# 07sdcard.net
KiCad netlist of a schematic drawn in Altium Designer
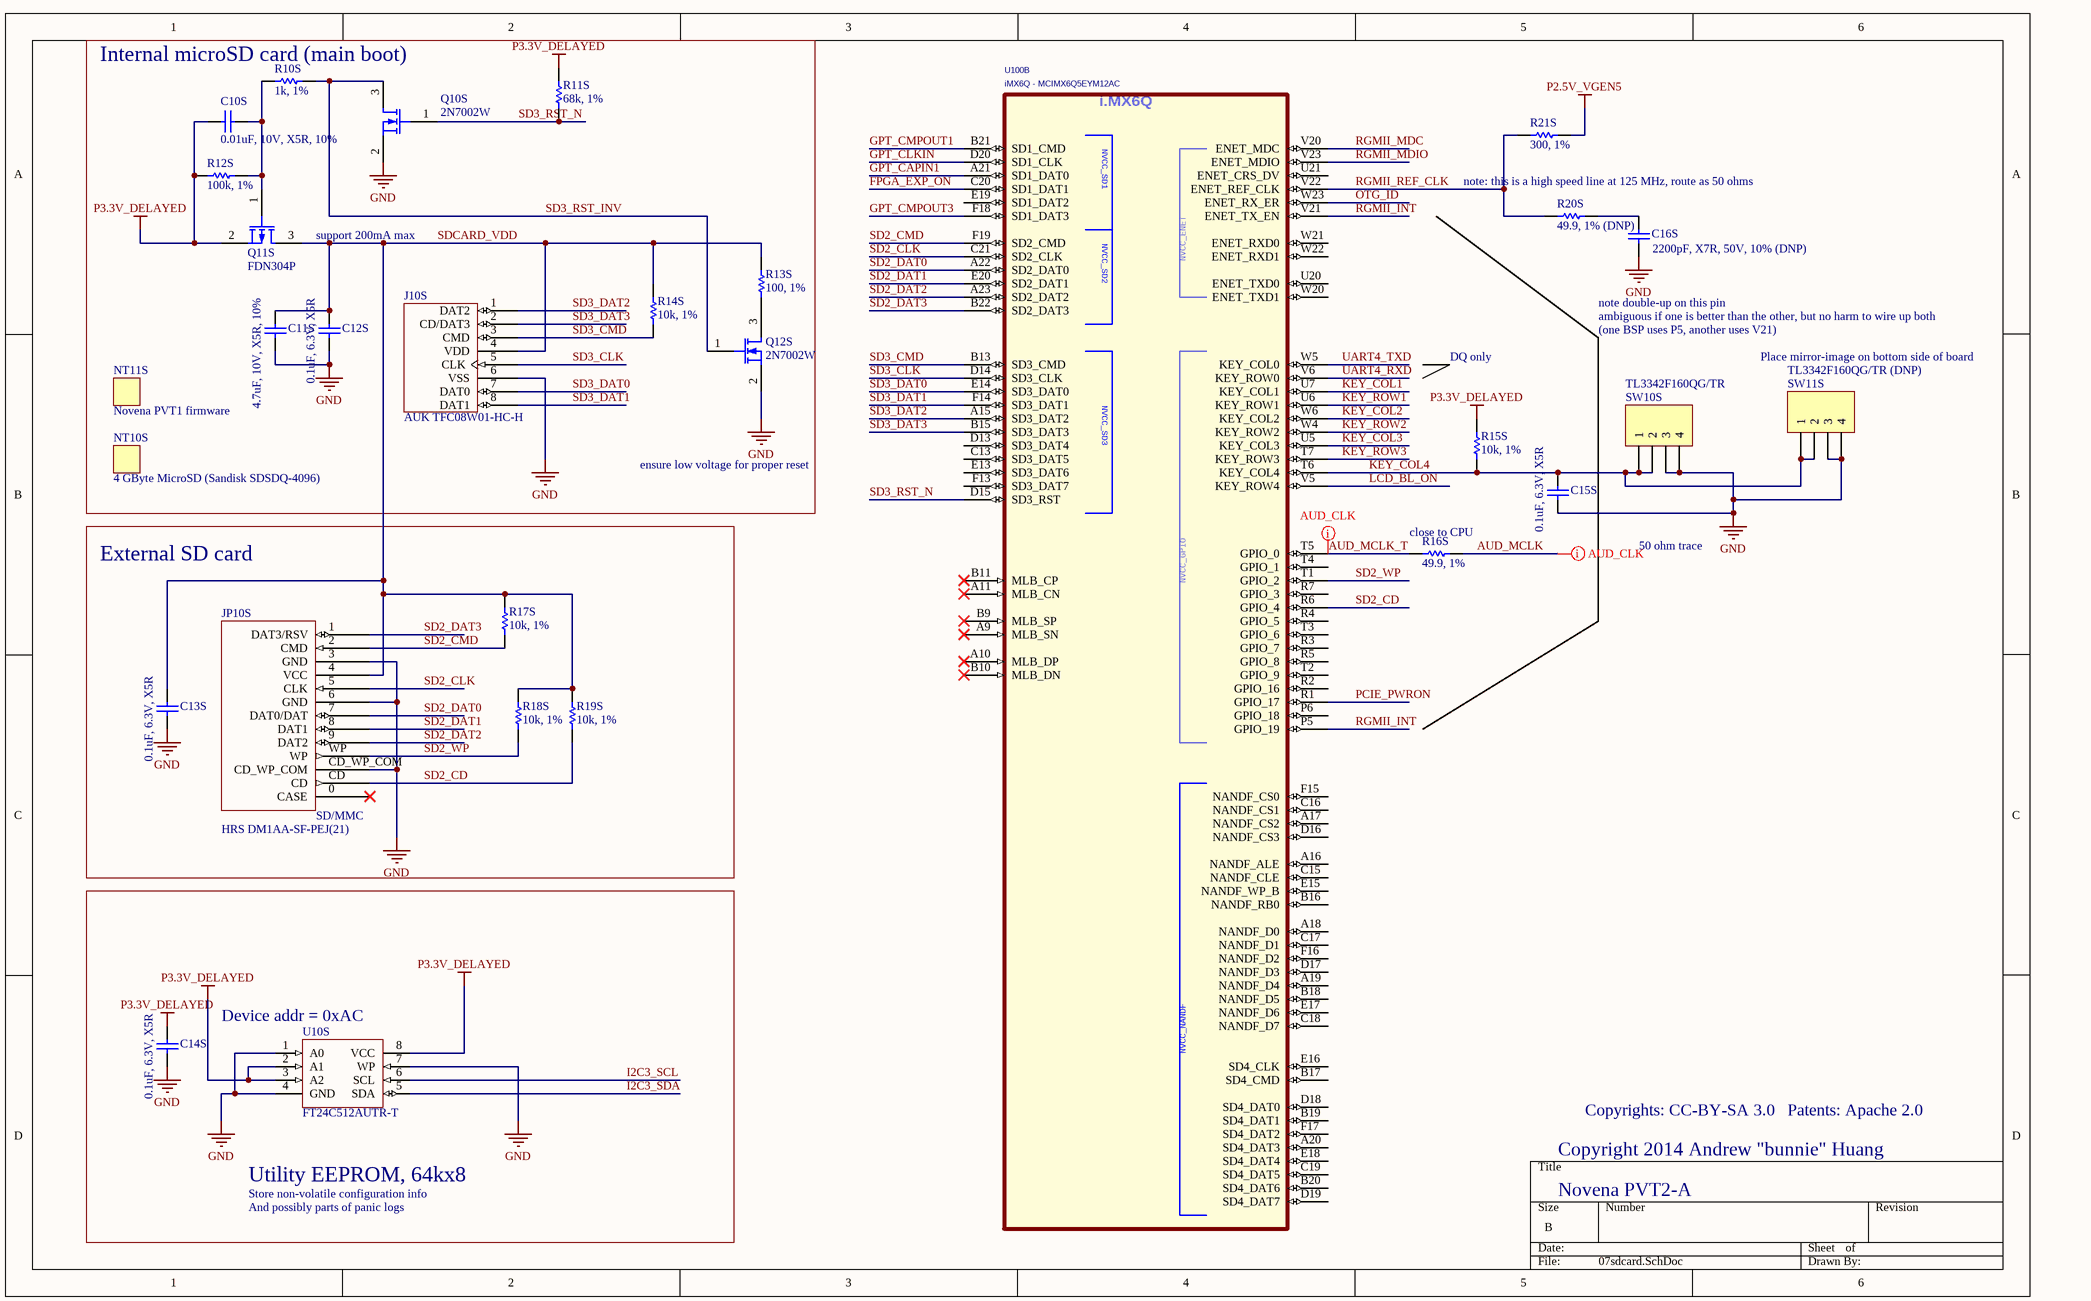
[diagram p0: 07sdcard.SchDoc]

(export (version "E")
  (design (tool "Eeschema 10.0.6"))
  (components
    (comp (ref "C10S")
      (value "0.01uF, 10V, X5R, 10%")
      (footprint "CAPC0603N_B")
      (description "Capacitor (Semiconductor SIM Model)")
      (fields (field (name "PUBLISHER") "Altium Limited"))
      (libsource (lib "Miscellaneous Devices") (part "Cap Semi"))
    )
    (comp (ref "C11S")
      (value "4.7uF, 10V, X5R, 10%")
      (footprint "CAPC1608N")
      (description "Capacitor (Semiconductor SIM Model)")
      (fields (field (name "PUBLISHER") "Altium Limited"))
      (libsource (lib "Miscellaneous Devices") (part "Cap Semi"))
    )
    (comp (ref "C12S")
      (value "0.1uF, 6.3V, X5R")
      (footprint "CAPC0603N_B")
      (description "Capacitor (Semiconductor SIM Model)")
      (fields (field (name "PUBLISHER") "Altium Limited"))
      (libsource (lib "Miscellaneous Devices") (part "Cap Semi"))
    )
    (comp (ref "C13S")
      (value "0.1uF, 6.3V, X5R")
      (footprint "CAPC0603N_B")
      (description "Capacitor (Semiconductor SIM Model)")
      (fields (field (name "PUBLISHER") "Altium Limited"))
      (libsource (lib "Miscellaneous Devices") (part "Cap Semi"))
    )
    (comp (ref "C14S")
      (value "0.1uF, 6.3V, X5R")
      (footprint "CAPC0603N_B")
      (description "Capacitor (Semiconductor SIM Model)")
      (fields (field (name "PUBLISHER") "Altium Limited"))
      (libsource (lib "Miscellaneous Devices") (part "Cap Semi"))
    )
    (comp (ref "C15S")
      (value "0.1uF, 6.3V, X5R")
      (footprint "CAPC0603N_B")
      (description "Capacitor (Semiconductor SIM Model)")
      (fields (field (name "PUBLISHER") "Altium Limited"))
      (libsource (lib "Miscellaneous Devices") (part "Cap Semi"))
    )
    (comp (ref "C16S")
      (value "2200pF, X7R, 50V, 10% (DNP)")
      (footprint "CAPC1005N")
      (description "Capacitor (Semiconductor SIM Model)")
      (fields (field (name "PUBLISHER") "Altium Limited"))
      (libsource (lib "Miscellaneous Devices") (part "Cap Semi"))
    )
    (comp (ref "J10S")
      (value "AUK TFC08W01-HC-H")
      (footprint "AUK_TFC08W01-HC-H")
      (description "Captive Micro-SD card for firmware images")
      (libsource (lib "commonsch") (part "MICRO_SD"))
    )
    (comp (ref "JP10S")
      (value "HRS DM1AA-SF-PEJ(21)")
      (footprint "HRS_DM1AA_SF_PEJ(21)")
      (description "SD card connector")
      (libsource (lib "commonsch") (part "HRS_DM1AA_SF_PEJ(21)"))
    )
    (comp (ref "NT10S")
      (value "4 GByte MicroSD (Sandisk SDSDQ-4096)")
      (description "Placeholder for non-electrical BOM items")
      (libsource (lib "commonsch") (part "NOTE"))
    )
    (comp (ref "NT11S")
      (value "Novena PVT1 firmware")
      (description "Placeholder for non-electrical BOM items")
      (libsource (lib "commonsch") (part "NOTE"))
    )
    (comp (ref "Q10S")
      (value "2N7002W")
      (footprint "SOT323-3AN")
      (description "N-Channel MOSFET")
      (fields (field (name "PUBLISHER") "Altium Limited"))
      (libsource (lib "Miscellaneous Devices") (part "MOSFET-N"))
    )
    (comp (ref "Q11S")
      (value "FDN304P")
      (footprint "SOT23-3N")
      (description "P-Channel MOSFET")
      (fields (field (name "PUBLISHER") "Altium Limited"))
      (libsource (lib "Miscellaneous Devices") (part "MOSFET-P"))
    )
    (comp (ref "Q12S")
      (value "2N7002W")
      (footprint "SOT323-3AN")
      (description "N-Channel MOSFET")
      (fields (field (name "PUBLISHER") "Altium Limited"))
      (libsource (lib "Miscellaneous Devices") (part "MOSFET-N"))
    )
    (comp (ref "R10S")
      (value "1k, 1%")
      (footprint "RESC1005N")
      (description "Resistor")
      (fields (field (name "PUBLISHER") "Altium Limited"))
      (libsource (lib "Miscellaneous Devices") (part "Res1"))
    )
    (comp (ref "R11S")
      (value "68k, 1%")
      (footprint "RESC1005N")
      (description "Resistor")
      (fields (field (name "PUBLISHER") "Altium Limited"))
      (libsource (lib "Miscellaneous Devices") (part "Res1"))
    )
    (comp (ref "R12S")
      (value "100k, 1%")
      (footprint "RESC1005N")
      (description "Resistor")
      (fields (field (name "PUBLISHER") "Altium Limited"))
      (libsource (lib "Miscellaneous Devices") (part "Res1"))
    )
    (comp (ref "R13S")
      (value "100, 1%")
      (footprint "RESC1005N")
      (description "Resistor")
      (fields (field (name "PUBLISHER") "Altium Limited"))
      (libsource (lib "Miscellaneous Devices") (part "Res1"))
    )
    (comp (ref "R14S")
      (value "10k, 1%")
      (footprint "RESC1005N")
      (description "Resistor")
      (fields (field (name "PUBLISHER") "Altium Limited"))
      (libsource (lib "Miscellaneous Devices") (part "Res1"))
    )
    (comp (ref "R15S")
      (value "10k, 1%")
      (footprint "RESC1005N")
      (description "Resistor")
      (fields (field (name "PUBLISHER") "Altium Limited"))
      (libsource (lib "Miscellaneous Devices") (part "Res1"))
    )
    (comp (ref "R16S")
      (value "49.9, 1%")
      (footprint "RESC1005N")
      (description "Resistor")
      (fields (field (name "PUBLISHER") "Altium Limited"))
      (libsource (lib "Miscellaneous Devices") (part "Res1"))
    )
    (comp (ref "R17S")
      (value "10k, 1%")
      (footprint "RESC1005N")
      (description "Resistor")
      (fields (field (name "PUBLISHER") "Altium Limited"))
      (libsource (lib "Miscellaneous Devices") (part "Res1"))
    )
    (comp (ref "R18S")
      (value "10k, 1%")
      (footprint "RESC1005N")
      (description "Resistor")
      (fields (field (name "PUBLISHER") "Altium Limited"))
      (libsource (lib "Miscellaneous Devices") (part "Res1"))
    )
    (comp (ref "R19S")
      (value "10k, 1%")
      (footprint "RESC1005N")
      (description "Resistor")
      (fields (field (name "PUBLISHER") "Altium Limited"))
      (libsource (lib "Miscellaneous Devices") (part "Res1"))
    )
    (comp (ref "R20S")
      (value "49.9, 1% (DNP)")
      (footprint "RESC1005N")
      (description "Resistor")
      (fields (field (name "PUBLISHER") "Altium Limited"))
      (libsource (lib "Miscellaneous Devices") (part "Res1"))
    )
    (comp (ref "R21S")
      (value "300, 1%")
      (footprint "RESC1005N")
      (description "Resistor")
      (fields (field (name "PUBLISHER") "Altium Limited"))
      (libsource (lib "Miscellaneous Devices") (part "Res1"))
    )
    (comp (ref "SW10S")
      (value "TL3342F160QG/TR")
      (footprint "SWITCH_TS-1187A")
      (description "Chi Fung TS-1187A")
      (fields (field (name "PUBLISHER") "Altium Limited"))
      (libsource (lib "Miscellaneous Connectors") (part "Header 4"))
    )
    (comp (ref "SW11S")
      (value "TL3342F160QG/TR (DNP)")
      (footprint "SWITCH_TS-1187A")
      (description "Chi Fung TS-1187A")
      (fields (field (name "PUBLISHER") "Altium Limited"))
      (libsource (lib "Miscellaneous Connectors") (part "Header 4"))
    )
    (comp (ref "U10S")
      (value "FT24C512AUTR-T")
      (footprint "TSOP65P640-8AN")
      (description "8kbit (1kx8) I2C EEPROM")
      (libsource (lib "*") (part "AT24C08"))
    )
    (comp (ref "U100")
      (value "iMX6Q - MCIMX6Q5EYM12AC")
      (description "PCIMX6Q5EVT10AC")
      (libsource (lib "*") (part "PCIMX6Q6VV1A"))
    )
  )
  (nets
    (net (code "1") (name "/AUD_MCLK") (class "Default")
      (node (ref "R16S") (pin "1") (pinfunction "1_1") (pintype "passive"))
    )
    (net (code "2") (name "/AUD_MCLK_T") (class "Default")
      (node (ref "R16S") (pin "2") (pinfunction "2_2") (pintype "passive"))
      (node (ref "U100") (pin "T5") (pinfunction "GPIO_0_T5") (pintype "bidirectional"))
    )
    (net (code "3") (name "/FPGA_EXP_ON") (class "Default")
      (node (ref "U100") (pin "C20") (pinfunction "SD1_DAT1_C20") (pintype "bidirectional"))
    )
    (net (code "4") (name "/GPT_CAPIN1") (class "Default")
      (node (ref "U100") (pin "A21") (pinfunction "SD1_DAT0_A21") (pintype "bidirectional"))
    )
    (net (code "5") (name "/GPT_CLKIN") (class "Default")
      (node (ref "U100") (pin "D20") (pinfunction "SD1_CLK_D20") (pintype "bidirectional"))
    )
    (net (code "6") (name "/GPT_CMPOUT1") (class "Default")
      (node (ref "U100") (pin "B21") (pinfunction "SD1_CMD_B21") (pintype "bidirectional"))
    )
    (net (code "7") (name "/GPT_CMPOUT3") (class "Default")
      (node (ref "U100") (pin "F18") (pinfunction "SD1_DAT3_F18") (pintype "bidirectional"))
    )
    (net (code "8") (name "/I2C3_SCL") (class "Default")
      (node (ref "U10S") (pin "6") (pinfunction "SCL_6") (pintype "input"))
    )
    (net (code "9") (name "/I2C3_SDA") (class "Default")
      (node (ref "U10S") (pin "5") (pinfunction "SDA_5") (pintype "bidirectional"))
    )
    (net (code "10") (name "/KEY_COL1") (class "Default")
      (node (ref "U100") (pin "U7") (pinfunction "KEY_COL1_U7") (pintype "bidirectional"))
    )
    (net (code "11") (name "/KEY_COL2") (class "Default")
      (node (ref "U100") (pin "W6") (pinfunction "KEY_COL2_W6") (pintype "bidirectional"))
    )
    (net (code "12") (name "/KEY_COL3") (class "Default")
      (node (ref "U100") (pin "U5") (pinfunction "KEY_COL3_U5") (pintype "bidirectional"))
    )
    (net (code "13") (name "/KEY_COL4") (class "Default")
      (node (ref "C15S") (pin "1") (pinfunction "1_1") (pintype "passive"))
      (node (ref "R15S") (pin "2") (pinfunction "2_2") (pintype "passive"))
      (node (ref "SW10S") (pin "1") (pinfunction "1_1") (pintype "passive"))
      (node (ref "SW10S") (pin "2") (pinfunction "2_2") (pintype "passive"))
      (node (ref "SW11S") (pin "1") (pinfunction "1_1") (pintype "passive"))
      (node (ref "SW11S") (pin "2") (pinfunction "2_2") (pintype "passive"))
      (node (ref "U100") (pin "T6") (pinfunction "KEY_COL4_T6") (pintype "bidirectional"))
    )
    (net (code "14") (name "/KEY_ROW1") (class "Default")
      (node (ref "U100") (pin "U6") (pinfunction "KEY_ROW1_U6") (pintype "bidirectional"))
    )
    (net (code "15") (name "/KEY_ROW2") (class "Default")
      (node (ref "U100") (pin "W4") (pinfunction "KEY_ROW2_W4") (pintype "bidirectional"))
    )
    (net (code "16") (name "/KEY_ROW3") (class "Default")
      (node (ref "U100") (pin "T7") (pinfunction "KEY_ROW3_T7") (pintype "bidirectional"))
    )
    (net (code "17") (name "/LCD_BL_ON") (class "Default")
      (node (ref "U100") (pin "V5") (pinfunction "KEY_ROW4_V5") (pintype "bidirectional"))
    )
    (net (code "18") (name "/OTG_ID") (class "Default")
      (node (ref "U100") (pin "W23") (pinfunction "ENET_RX_ER_W23") (pintype "bidirectional"))
    )
    (net (code "19") (name "/PCIE_PWRON") (class "Default")
      (node (ref "U100") (pin "R1") (pinfunction "GPIO_17_R1") (pintype "bidirectional"))
    )
    (net (code "20") (name "/RGMII_INT") (class "Default")
      (node (ref "U100") (pin "P5") (pinfunction "GPIO_19_P5") (pintype "bidirectional"))
      (node (ref "U100") (pin "V21") (pinfunction "ENET_TX_EN_V21") (pintype "bidirectional"))
    )
    (net (code "21") (name "/RGMII_MDC") (class "Default")
      (node (ref "U100") (pin "V20") (pinfunction "ENET_MDC_V20") (pintype "bidirectional"))
    )
    (net (code "22") (name "/RGMII_MDIO") (class "Default")
      (node (ref "U100") (pin "V23") (pinfunction "ENET_MDIO_V23") (pintype "bidirectional"))
    )
    (net (code "23") (name "/RGMII_REF_CLK") (class "Default")
      (node (ref "R20S") (pin "1") (pinfunction "1_1") (pintype "passive"))
      (node (ref "R21S") (pin "1") (pinfunction "1_1") (pintype "passive"))
      (node (ref "U100") (pin "V22") (pinfunction "ENET_REF_CLK_V22") (pintype "bidirectional"))
    )
    (net (code "24") (name "/SD2_CD") (class "Default")
      (node (ref "JP10S") (pin "CD") (pinfunction "CD_CD") (pintype "output"))
      (node (ref "R19S") (pin "2") (pinfunction "2_2") (pintype "passive"))
      (node (ref "U100") (pin "R6") (pinfunction "GPIO_4_R6") (pintype "bidirectional"))
    )
    (net (code "25") (name "/SD2_CLK") (class "Default")
      (node (ref "JP10S") (pin "5") (pinfunction "CLK_5") (pintype "input"))
      (node (ref "U100") (pin "C21") (pinfunction "SD2_CLK_C21") (pintype "bidirectional"))
    )
    (net (code "26") (name "/SD2_CMD") (class "Default")
      (node (ref "JP10S") (pin "2") (pinfunction "CMD_2") (pintype "input"))
      (node (ref "R17S") (pin "2") (pinfunction "2_2") (pintype "passive"))
      (node (ref "U100") (pin "F19") (pinfunction "SD2_CMD_F19") (pintype "bidirectional"))
    )
    (net (code "27") (name "/SD2_DAT0") (class "Default")
      (node (ref "JP10S") (pin "7") (pinfunction "DAT0/DAT_7") (pintype "bidirectional"))
      (node (ref "U100") (pin "A22") (pinfunction "SD2_DAT0_A22") (pintype "bidirectional"))
    )
    (net (code "28") (name "/SD2_DAT1") (class "Default")
      (node (ref "JP10S") (pin "8") (pinfunction "DAT1_8") (pintype "bidirectional"))
      (node (ref "U100") (pin "E20") (pinfunction "SD2_DAT1_E20") (pintype "bidirectional"))
    )
    (net (code "29") (name "/SD2_DAT2") (class "Default")
      (node (ref "JP10S") (pin "9") (pinfunction "DAT2_9") (pintype "bidirectional"))
      (node (ref "U100") (pin "A23") (pinfunction "SD2_DAT2_A23") (pintype "bidirectional"))
    )
    (net (code "30") (name "/SD2_DAT3") (class "Default")
      (node (ref "JP10S") (pin "1") (pinfunction "DAT3/RSV_1") (pintype "bidirectional"))
      (node (ref "U100") (pin "B22") (pinfunction "SD2_DAT3_B22") (pintype "bidirectional"))
    )
    (net (code "31") (name "/SD2_WP") (class "Default")
      (node (ref "JP10S") (pin "WP") (pinfunction "WP_WP") (pintype "output"))
      (node (ref "R18S") (pin "2") (pinfunction "2_2") (pintype "passive"))
      (node (ref "U100") (pin "T1") (pinfunction "GPIO_2_T1") (pintype "bidirectional"))
    )
    (net (code "32") (name "/SD3_CLK") (class "Default")
      (node (ref "J10S") (pin "5") (pinfunction "CLK_5") (pintype "input"))
      (node (ref "U100") (pin "D14") (pinfunction "SD3_CLK_D14") (pintype "bidirectional"))
    )
    (net (code "33") (name "/SD3_CMD") (class "Default")
      (node (ref "J10S") (pin "3") (pinfunction "CMD_3") (pintype "bidirectional"))
      (node (ref "R14S") (pin "2") (pinfunction "2_2") (pintype "passive"))
      (node (ref "U100") (pin "B13") (pinfunction "SD3_CMD_B13") (pintype "bidirectional"))
    )
    (net (code "34") (name "/SD3_DAT0") (class "Default")
      (node (ref "J10S") (pin "7") (pinfunction "DAT0_7") (pintype "bidirectional"))
      (node (ref "U100") (pin "E14") (pinfunction "SD3_DAT0_E14") (pintype "bidirectional"))
    )
    (net (code "35") (name "/SD3_DAT1") (class "Default")
      (node (ref "J10S") (pin "8") (pinfunction "DAT1_8") (pintype "bidirectional"))
      (node (ref "U100") (pin "F14") (pinfunction "SD3_DAT1_F14") (pintype "bidirectional"))
    )
    (net (code "36") (name "/SD3_DAT2") (class "Default")
      (node (ref "J10S") (pin "1") (pinfunction "DAT2_1") (pintype "bidirectional"))
      (node (ref "U100") (pin "A15") (pinfunction "SD3_DAT2_A15") (pintype "bidirectional"))
    )
    (net (code "37") (name "/SD3_DAT3") (class "Default")
      (node (ref "J10S") (pin "2") (pinfunction "CD/DAT3_2") (pintype "bidirectional"))
      (node (ref "U100") (pin "B15") (pinfunction "SD3_DAT3_B15") (pintype "bidirectional"))
    )
    (net (code "38") (name "/SD3_RST_INV") (class "Default")
      (node (ref "Q10S") (pin "3") (pinfunction "D_3") (pintype "passive"))
      (node (ref "Q12S") (pin "1") (pinfunction "G_1") (pintype "passive"))
      (node (ref "R10S") (pin "1") (pinfunction "1_1") (pintype "passive"))
    )
    (net (code "39") (name "/SD3_RST_N") (class "Default")
      (node (ref "Q10S") (pin "1") (pinfunction "G_1") (pintype "passive"))
      (node (ref "R11S") (pin "2") (pinfunction "2_2") (pintype "passive"))
      (node (ref "U100") (pin "D15") (pinfunction "SD3_RST_D15") (pintype "bidirectional"))
    )
    (net (code "40") (name "/SDCARD_VDD") (class "Default")
      (node (ref "C11S") (pin "1") (pinfunction "1_1") (pintype "passive"))
      (node (ref "C12S") (pin "1") (pinfunction "1_1") (pintype "passive"))
      (node (ref "C13S") (pin "1") (pinfunction "1_1") (pintype "passive"))
      (node (ref "J10S") (pin "4") (pinfunction "VDD_4") (pintype "power_in"))
      (node (ref "JP10S") (pin "4") (pinfunction "VCC_4") (pintype "power_in"))
      (node (ref "Q11S") (pin "3") (pinfunction "D_3") (pintype "passive"))
      (node (ref "R13S") (pin "1") (pinfunction "1_1") (pintype "passive"))
      (node (ref "R14S") (pin "1") (pinfunction "1_1") (pintype "passive"))
      (node (ref "R17S") (pin "1") (pinfunction "1_1") (pintype "passive"))
      (node (ref "R18S") (pin "1") (pinfunction "1_1") (pintype "passive"))
      (node (ref "R19S") (pin "1") (pinfunction "1_1") (pintype "passive"))
    )
    (net (code "41") (name "/UART4_RXD") (class "Default")
      (node (ref "U100") (pin "V6") (pinfunction "KEY_ROW0_V6") (pintype "bidirectional"))
    )
    (net (code "42") (name "/UART4_TXD") (class "Default")
      (node (ref "U100") (pin "W5") (pinfunction "KEY_COL0_W5") (pintype "bidirectional"))
    )
    (net (code "43") (name "GND") (class "Default")
      (node (ref "C11S") (pin "2") (pinfunction "2_2") (pintype "passive"))
      (node (ref "C12S") (pin "2") (pinfunction "2_2") (pintype "passive"))
      (node (ref "C13S") (pin "2") (pinfunction "2_2") (pintype "passive"))
      (node (ref "C14S") (pin "2") (pinfunction "2_2") (pintype "passive"))
      (node (ref "C15S") (pin "2") (pinfunction "2_2") (pintype "passive"))
      (node (ref "C16S") (pin "1") (pinfunction "1_1") (pintype "passive"))
      (node (ref "J10S") (pin "6") (pinfunction "VSS_6") (pintype "power_in"))
      (node (ref "JP10S") (pin "3") (pinfunction "GND_3") (pintype "power_in"))
      (node (ref "JP10S") (pin "6") (pinfunction "GND_6") (pintype "power_in"))
      (node (ref "JP10S") (pin "CD_WP_COM") (pinfunction "CD_WP_COM_CD_WP_COM") (pintype "power_in"))
      (node (ref "Q10S") (pin "2") (pinfunction "S_2") (pintype "passive"))
      (node (ref "Q12S") (pin "2") (pinfunction "S_2") (pintype "passive"))
      (node (ref "SW10S") (pin "3") (pinfunction "3_3") (pintype "passive"))
      (node (ref "SW10S") (pin "4") (pinfunction "4_4") (pintype "passive"))
      (node (ref "SW11S") (pin "3") (pinfunction "3_3") (pintype "passive"))
      (node (ref "SW11S") (pin "4") (pinfunction "4_4") (pintype "passive"))
      (node (ref "U10S") (pin "1") (pinfunction "A0_1") (pintype "input"))
      (node (ref "U10S") (pin "4") (pinfunction "GND_4") (pintype "power_in"))
      (node (ref "U10S") (pin "7") (pinfunction "WP_7") (pintype "input"))
    )
    (net (code "44") (name "Net-(C16S-Pad2)") (class "Default")
      (node (ref "C16S") (pin "2") (pinfunction "2_2") (pintype "passive"))
      (node (ref "R20S") (pin "2") (pinfunction "2_2") (pintype "passive"))
    )
    (net (code "45") (name "Net-(Q11S-G)") (class "Default")
      (node (ref "C10S") (pin "1") (pinfunction "1_1") (pintype "passive"))
      (node (ref "Q11S") (pin "1") (pinfunction "G_1") (pintype "passive"))
      (node (ref "R10S") (pin "2") (pinfunction "2_2") (pintype "passive"))
      (node (ref "R12S") (pin "1") (pinfunction "1_1") (pintype "passive"))
    )
    (net (code "46") (name "Net-(Q12S-D)") (class "Default")
      (node (ref "Q12S") (pin "3") (pinfunction "D_3") (pintype "passive"))
      (node (ref "R13S") (pin "2") (pinfunction "2_2") (pintype "passive"))
    )
    (net (code "47") (name "P2.5V_VGEN5") (class "Default")
      (node (ref "R21S") (pin "2") (pinfunction "2_2") (pintype "passive"))
    )
    (net (code "48") (name "P3.3V_DELAYED") (class "Default")
      (node (ref "C10S") (pin "2") (pinfunction "2_2") (pintype "passive"))
      (node (ref "C14S") (pin "1") (pinfunction "1_1") (pintype "passive"))
      (node (ref "Q11S") (pin "2") (pinfunction "S_2") (pintype "passive"))
      (node (ref "R11S") (pin "1") (pinfunction "1_1") (pintype "passive"))
      (node (ref "R12S") (pin "2") (pinfunction "2_2") (pintype "passive"))
      (node (ref "R15S") (pin "1") (pinfunction "1_1") (pintype "passive"))
      (node (ref "U10S") (pin "2") (pinfunction "A1_2") (pintype "input"))
      (node (ref "U10S") (pin "3") (pinfunction "A2_3") (pintype "input"))
      (node (ref "U10S") (pin "8") (pinfunction "VCC_8") (pintype "power_in"))
    )
    (net (code "49") (name "unconnected-(JP10S-CASE-Pad0)") (class "Default")
      (node (ref "JP10S") (pin "0") (pinfunction "CASE_0") (pintype "power_in+no_connect"))
    )
    (net (code "50") (name "unconnected-(U100B-ENET_CRS_DV-PadU21)") (class "Default")
      (node (ref "U100") (pin "U21") (pinfunction "ENET_CRS_DV_U21") (pintype "bidirectional"))
    )
    (net (code "51") (name "unconnected-(U100B-ENET_RXD0-PadW21)") (class "Default")
      (node (ref "U100") (pin "W21") (pinfunction "ENET_RXD0_W21") (pintype "bidirectional"))
    )
    (net (code "52") (name "unconnected-(U100B-ENET_RXD1-PadW22)") (class "Default")
      (node (ref "U100") (pin "W22") (pinfunction "ENET_RXD1_W22") (pintype "bidirectional"))
    )
    (net (code "53") (name "unconnected-(U100B-ENET_TXD0-PadU20)") (class "Default")
      (node (ref "U100") (pin "U20") (pinfunction "ENET_TXD0_U20") (pintype "bidirectional"))
    )
    (net (code "54") (name "unconnected-(U100B-ENET_TXD1-PadW20)") (class "Default")
      (node (ref "U100") (pin "W20") (pinfunction "ENET_TXD1_W20") (pintype "bidirectional"))
    )
    (net (code "55") (name "unconnected-(U100B-GPIO_1-PadT4)") (class "Default")
      (node (ref "U100") (pin "T4") (pinfunction "GPIO_1_T4") (pintype "bidirectional"))
    )
    (net (code "56") (name "unconnected-(U100B-GPIO_3-PadR7)") (class "Default")
      (node (ref "U100") (pin "R7") (pinfunction "GPIO_3_R7") (pintype "bidirectional"))
    )
    (net (code "57") (name "unconnected-(U100B-GPIO_5-PadR4)") (class "Default")
      (node (ref "U100") (pin "R4") (pinfunction "GPIO_5_R4") (pintype "bidirectional"))
    )
    (net (code "58") (name "unconnected-(U100B-GPIO_6-PadT3)") (class "Default")
      (node (ref "U100") (pin "T3") (pinfunction "GPIO_6_T3") (pintype "bidirectional"))
    )
    (net (code "59") (name "unconnected-(U100B-GPIO_7-PadR3)") (class "Default")
      (node (ref "U100") (pin "R3") (pinfunction "GPIO_7_R3") (pintype "bidirectional"))
    )
    (net (code "60") (name "unconnected-(U100B-GPIO_8-PadR5)") (class "Default")
      (node (ref "U100") (pin "R5") (pinfunction "GPIO_8_R5") (pintype "bidirectional"))
    )
    (net (code "61") (name "unconnected-(U100B-GPIO_9-PadT2)") (class "Default")
      (node (ref "U100") (pin "T2") (pinfunction "GPIO_9_T2") (pintype "bidirectional"))
    )
    (net (code "62") (name "unconnected-(U100B-GPIO_16-PadR2)") (class "Default")
      (node (ref "U100") (pin "R2") (pinfunction "GPIO_16_R2") (pintype "bidirectional"))
    )
    (net (code "63") (name "unconnected-(U100B-GPIO_18-PadP6)") (class "Default")
      (node (ref "U100") (pin "P6") (pinfunction "GPIO_18_P6") (pintype "bidirectional"))
    )
    (net (code "64") (name "unconnected-(U100B-MLB_CN-PadA11)") (class "Default")
      (node (ref "U100") (pin "A11") (pinfunction "MLB_CN_A11") (pintype "input+no_connect"))
    )
    (net (code "65") (name "unconnected-(U100B-MLB_CP-PadB11)") (class "Default")
      (node (ref "U100") (pin "B11") (pinfunction "MLB_CP_B11") (pintype "input+no_connect"))
    )
    (net (code "66") (name "unconnected-(U100B-MLB_DN-PadB10)") (class "Default")
      (node (ref "U100") (pin "B10") (pinfunction "MLB_DN_B10") (pintype "input+no_connect"))
    )
    (net (code "67") (name "unconnected-(U100B-MLB_DP-PadA10)") (class "Default")
      (node (ref "U100") (pin "A10") (pinfunction "MLB_DP_A10") (pintype "input+no_connect"))
    )
    (net (code "68") (name "unconnected-(U100B-MLB_SN-PadA9)") (class "Default")
      (node (ref "U100") (pin "A9") (pinfunction "MLB_SN_A9") (pintype "input+no_connect"))
    )
    (net (code "69") (name "unconnected-(U100B-MLB_SP-PadB9)") (class "Default")
      (node (ref "U100") (pin "B9") (pinfunction "MLB_SP_B9") (pintype "input+no_connect"))
    )
    (net (code "70") (name "unconnected-(U100B-NANDF_ALE-PadA16)") (class "Default")
      (node (ref "U100") (pin "A16") (pinfunction "NANDF_ALE_A16") (pintype "bidirectional"))
    )
    (net (code "71") (name "unconnected-(U100B-NANDF_CLE-PadC15)") (class "Default")
      (node (ref "U100") (pin "C15") (pinfunction "NANDF_CLE_C15") (pintype "bidirectional"))
    )
    (net (code "72") (name "unconnected-(U100B-NANDF_CS0-PadF15)") (class "Default")
      (node (ref "U100") (pin "F15") (pinfunction "NANDF_CS0_F15") (pintype "bidirectional"))
    )
    (net (code "73") (name "unconnected-(U100B-NANDF_CS1-PadC16)") (class "Default")
      (node (ref "U100") (pin "C16") (pinfunction "NANDF_CS1_C16") (pintype "bidirectional"))
    )
    (net (code "74") (name "unconnected-(U100B-NANDF_CS2-PadA17)") (class "Default")
      (node (ref "U100") (pin "A17") (pinfunction "NANDF_CS2_A17") (pintype "bidirectional"))
    )
    (net (code "75") (name "unconnected-(U100B-NANDF_CS3-PadD16)") (class "Default")
      (node (ref "U100") (pin "D16") (pinfunction "NANDF_CS3_D16") (pintype "bidirectional"))
    )
    (net (code "76") (name "unconnected-(U100B-NANDF_D0-PadA18)") (class "Default")
      (node (ref "U100") (pin "A18") (pinfunction "NANDF_D0_A18") (pintype "bidirectional"))
    )
    (net (code "77") (name "unconnected-(U100B-NANDF_D1-PadC17)") (class "Default")
      (node (ref "U100") (pin "C17") (pinfunction "NANDF_D1_C17") (pintype "bidirectional"))
    )
    (net (code "78") (name "unconnected-(U100B-NANDF_D2-PadF16)") (class "Default")
      (node (ref "U100") (pin "F16") (pinfunction "NANDF_D2_F16") (pintype "bidirectional"))
    )
    (net (code "79") (name "unconnected-(U100B-NANDF_D3-PadD17)") (class "Default")
      (node (ref "U100") (pin "D17") (pinfunction "NANDF_D3_D17") (pintype "bidirectional"))
    )
    (net (code "80") (name "unconnected-(U100B-NANDF_D4-PadA19)") (class "Default")
      (node (ref "U100") (pin "A19") (pinfunction "NANDF_D4_A19") (pintype "bidirectional"))
    )
    (net (code "81") (name "unconnected-(U100B-NANDF_D5-PadB18)") (class "Default")
      (node (ref "U100") (pin "B18") (pinfunction "NANDF_D5_B18") (pintype "bidirectional"))
    )
    (net (code "82") (name "unconnected-(U100B-NANDF_D6-PadE17)") (class "Default")
      (node (ref "U100") (pin "E17") (pinfunction "NANDF_D6_E17") (pintype "bidirectional"))
    )
    (net (code "83") (name "unconnected-(U100B-NANDF_D7-PadC18)") (class "Default")
      (node (ref "U100") (pin "C18") (pinfunction "NANDF_D7_C18") (pintype "bidirectional"))
    )
    (net (code "84") (name "unconnected-(U100B-NANDF_RB0-PadB16)") (class "Default")
      (node (ref "U100") (pin "B16") (pinfunction "NANDF_RB0_B16") (pintype "bidirectional"))
    )
    (net (code "85") (name "unconnected-(U100B-NANDF_WP_B-PadE15)") (class "Default")
      (node (ref "U100") (pin "E15") (pinfunction "NANDF_WP_B_E15") (pintype "bidirectional"))
    )
    (net (code "86") (name "unconnected-(U100B-SD1_DAT2-PadE19)") (class "Default")
      (node (ref "U100") (pin "E19") (pinfunction "SD1_DAT2_E19") (pintype "bidirectional"))
    )
    (net (code "87") (name "unconnected-(U100B-SD3_DAT4-PadD13)") (class "Default")
      (node (ref "U100") (pin "D13") (pinfunction "SD3_DAT4_D13") (pintype "bidirectional"))
    )
    (net (code "88") (name "unconnected-(U100B-SD3_DAT5-PadC13)") (class "Default")
      (node (ref "U100") (pin "C13") (pinfunction "SD3_DAT5_C13") (pintype "bidirectional"))
    )
    (net (code "89") (name "unconnected-(U100B-SD3_DAT6-PadE13)") (class "Default")
      (node (ref "U100") (pin "E13") (pinfunction "SD3_DAT6_E13") (pintype "bidirectional"))
    )
    (net (code "90") (name "unconnected-(U100B-SD3_DAT7-PadF13)") (class "Default")
      (node (ref "U100") (pin "F13") (pinfunction "SD3_DAT7_F13") (pintype "bidirectional"))
    )
    (net (code "91") (name "unconnected-(U100B-SD4_CLK-PadE16)") (class "Default")
      (node (ref "U100") (pin "E16") (pinfunction "SD4_CLK_E16") (pintype "bidirectional"))
    )
    (net (code "92") (name "unconnected-(U100B-SD4_CMD-PadB17)") (class "Default")
      (node (ref "U100") (pin "B17") (pinfunction "SD4_CMD_B17") (pintype "bidirectional"))
    )
    (net (code "93") (name "unconnected-(U100B-SD4_DAT0-PadD18)") (class "Default")
      (node (ref "U100") (pin "D18") (pinfunction "SD4_DAT0_D18") (pintype "bidirectional"))
    )
    (net (code "94") (name "unconnected-(U100B-SD4_DAT1-PadB19)") (class "Default")
      (node (ref "U100") (pin "B19") (pinfunction "SD4_DAT1_B19") (pintype "bidirectional"))
    )
    (net (code "95") (name "unconnected-(U100B-SD4_DAT2-PadF17)") (class "Default")
      (node (ref "U100") (pin "F17") (pinfunction "SD4_DAT2_F17") (pintype "bidirectional"))
    )
    (net (code "96") (name "unconnected-(U100B-SD4_DAT3-PadA20)") (class "Default")
      (node (ref "U100") (pin "A20") (pinfunction "SD4_DAT3_A20") (pintype "bidirectional"))
    )
    (net (code "97") (name "unconnected-(U100B-SD4_DAT4-PadE18)") (class "Default")
      (node (ref "U100") (pin "E18") (pinfunction "SD4_DAT4_E18") (pintype "bidirectional"))
    )
    (net (code "98") (name "unconnected-(U100B-SD4_DAT5-PadC19)") (class "Default")
      (node (ref "U100") (pin "C19") (pinfunction "SD4_DAT5_C19") (pintype "bidirectional"))
    )
    (net (code "99") (name "unconnected-(U100B-SD4_DAT6-PadB20)") (class "Default")
      (node (ref "U100") (pin "B20") (pinfunction "SD4_DAT6_B20") (pintype "bidirectional"))
    )
    (net (code "100") (name "unconnected-(U100B-SD4_DAT7-PadD19)") (class "Default")
      (node (ref "U100") (pin "D19") (pinfunction "SD4_DAT7_D19") (pintype "bidirectional"))
    )
  )
)
